# CS_ANT.net
KiCad netlist of a schematic drawn in EAGLE
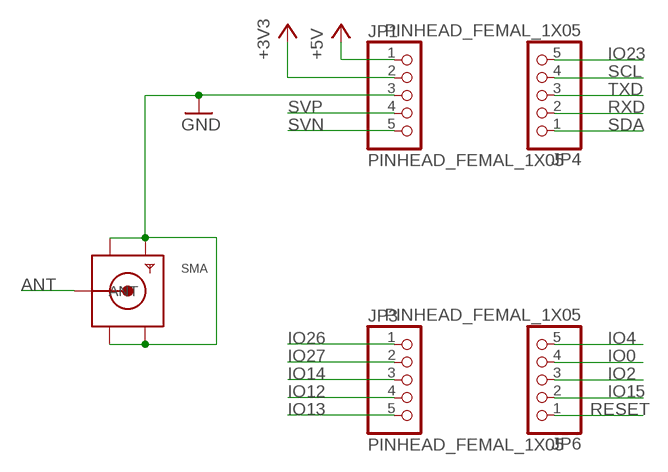
[diagram p0: schematic, sheet 1]

(export (version "E")
  (design (tool "Eeschema 10.0.6"))
  (components
    (comp (ref "JP1")
      (value "PINHEAD_FEMAL_1X05")
      (footprint "eagle-import:1X05F")
      (libsource (lib "eagle-import") (part "PINHEAD_FEMAL_1X05"))
    )
    (comp (ref "JP3")
      (value "PINHEAD_FEMAL_1X05")
      (footprint "eagle-import:1X05F")
      (libsource (lib "eagle-import") (part "PINHEAD_FEMAL_1X05"))
    )
    (comp (ref "JP4")
      (value "PINHEAD_FEMAL_1X05")
      (footprint "eagle-import:1X05F")
      (libsource (lib "eagle-import") (part "PINHEAD_FEMAL_1X05"))
    )
    (comp (ref "JP6")
      (value "PINHEAD_FEMAL_1X05")
      (footprint "eagle-import:1X05F")
      (libsource (lib "eagle-import") (part "PINHEAD_FEMAL_1X05"))
    )
    (comp (ref "SMA")
      (value "SMACONNECTOR")
      (footprint "eagle-import:SMA90_DIP")
      (libsource (lib "eagle-import") (part "SMACONNECTOR"))
    )
  )
  (nets
    (net (code "1") (name "+3V3") (class "Default")
      (node (ref "JP1") (pin "2") (pinfunction "2_2") (pintype "passive"))
    )
    (net (code "2") (name "+5V") (class "Default")
      (node (ref "JP1") (pin "1") (pinfunction "1_1") (pintype "passive"))
    )
    (net (code "3") (name "/ANT") (class "Default")
      (node (ref "SMA") (pin "ANTENNA") (pinfunction "ANT_ANTENNA") (pintype "bidirectional"))
    )
    (net (code "4") (name "/IO0") (class "Default")
      (node (ref "JP6") (pin "4") (pinfunction "4_4") (pintype "passive"))
    )
    (net (code "5") (name "/IO2") (class "Default")
      (node (ref "JP6") (pin "3") (pinfunction "3_3") (pintype "passive"))
    )
    (net (code "6") (name "/IO4") (class "Default")
      (node (ref "JP6") (pin "5") (pinfunction "5_5") (pintype "passive"))
    )
    (net (code "7") (name "/IO12") (class "Default")
      (node (ref "JP3") (pin "4") (pinfunction "4_4") (pintype "passive"))
    )
    (net (code "8") (name "/IO13") (class "Default")
      (node (ref "JP3") (pin "5") (pinfunction "5_5") (pintype "passive"))
    )
    (net (code "9") (name "/IO14") (class "Default")
      (node (ref "JP3") (pin "3") (pinfunction "3_3") (pintype "passive"))
    )
    (net (code "10") (name "/IO15") (class "Default")
      (node (ref "JP6") (pin "2") (pinfunction "2_2") (pintype "passive"))
    )
    (net (code "11") (name "/IO23") (class "Default")
      (node (ref "JP4") (pin "5") (pinfunction "5_5") (pintype "passive"))
    )
    (net (code "12") (name "/IO26") (class "Default")
      (node (ref "JP3") (pin "1") (pinfunction "1_1") (pintype "passive"))
    )
    (net (code "13") (name "/IO27") (class "Default")
      (node (ref "JP3") (pin "2") (pinfunction "2_2") (pintype "passive"))
    )
    (net (code "14") (name "/RESET") (class "Default")
      (node (ref "JP6") (pin "1") (pinfunction "1_1") (pintype "passive"))
    )
    (net (code "15") (name "/RXD") (class "Default")
      (node (ref "JP4") (pin "2") (pinfunction "2_2") (pintype "passive"))
    )
    (net (code "16") (name "/SCL") (class "Default")
      (node (ref "JP4") (pin "4") (pinfunction "4_4") (pintype "passive"))
    )
    (net (code "17") (name "/SDA") (class "Default")
      (node (ref "JP4") (pin "1") (pinfunction "1_1") (pintype "passive"))
    )
    (net (code "18") (name "/SVN") (class "Default")
      (node (ref "JP1") (pin "5") (pinfunction "5_5") (pintype "passive"))
    )
    (net (code "19") (name "/SVP") (class "Default")
      (node (ref "JP1") (pin "4") (pinfunction "4_4") (pintype "passive"))
    )
    (net (code "20") (name "/TXD") (class "Default")
      (node (ref "JP4") (pin "3") (pinfunction "3_3") (pintype "passive"))
    )
    (net (code "21") (name "GND") (class "Default")
      (node (ref "JP1") (pin "3") (pinfunction "3_3") (pintype "passive"))
      (node (ref "SMA") (pin "GND1") (pinfunction "GND1_GND1") (pintype "power_in"))
      (node (ref "SMA") (pin "GND2") (pinfunction "GND2_GND2") (pintype "power_in"))
      (node (ref "SMA") (pin "GND3") (pinfunction "GND3_GND3") (pintype "power_in"))
      (node (ref "SMA") (pin "GND4") (pinfunction "GND4_GND4") (pintype "power_in"))
    )
  )
)
